# source_eagle.net
KiCad netlist of a schematic drawn in EAGLE
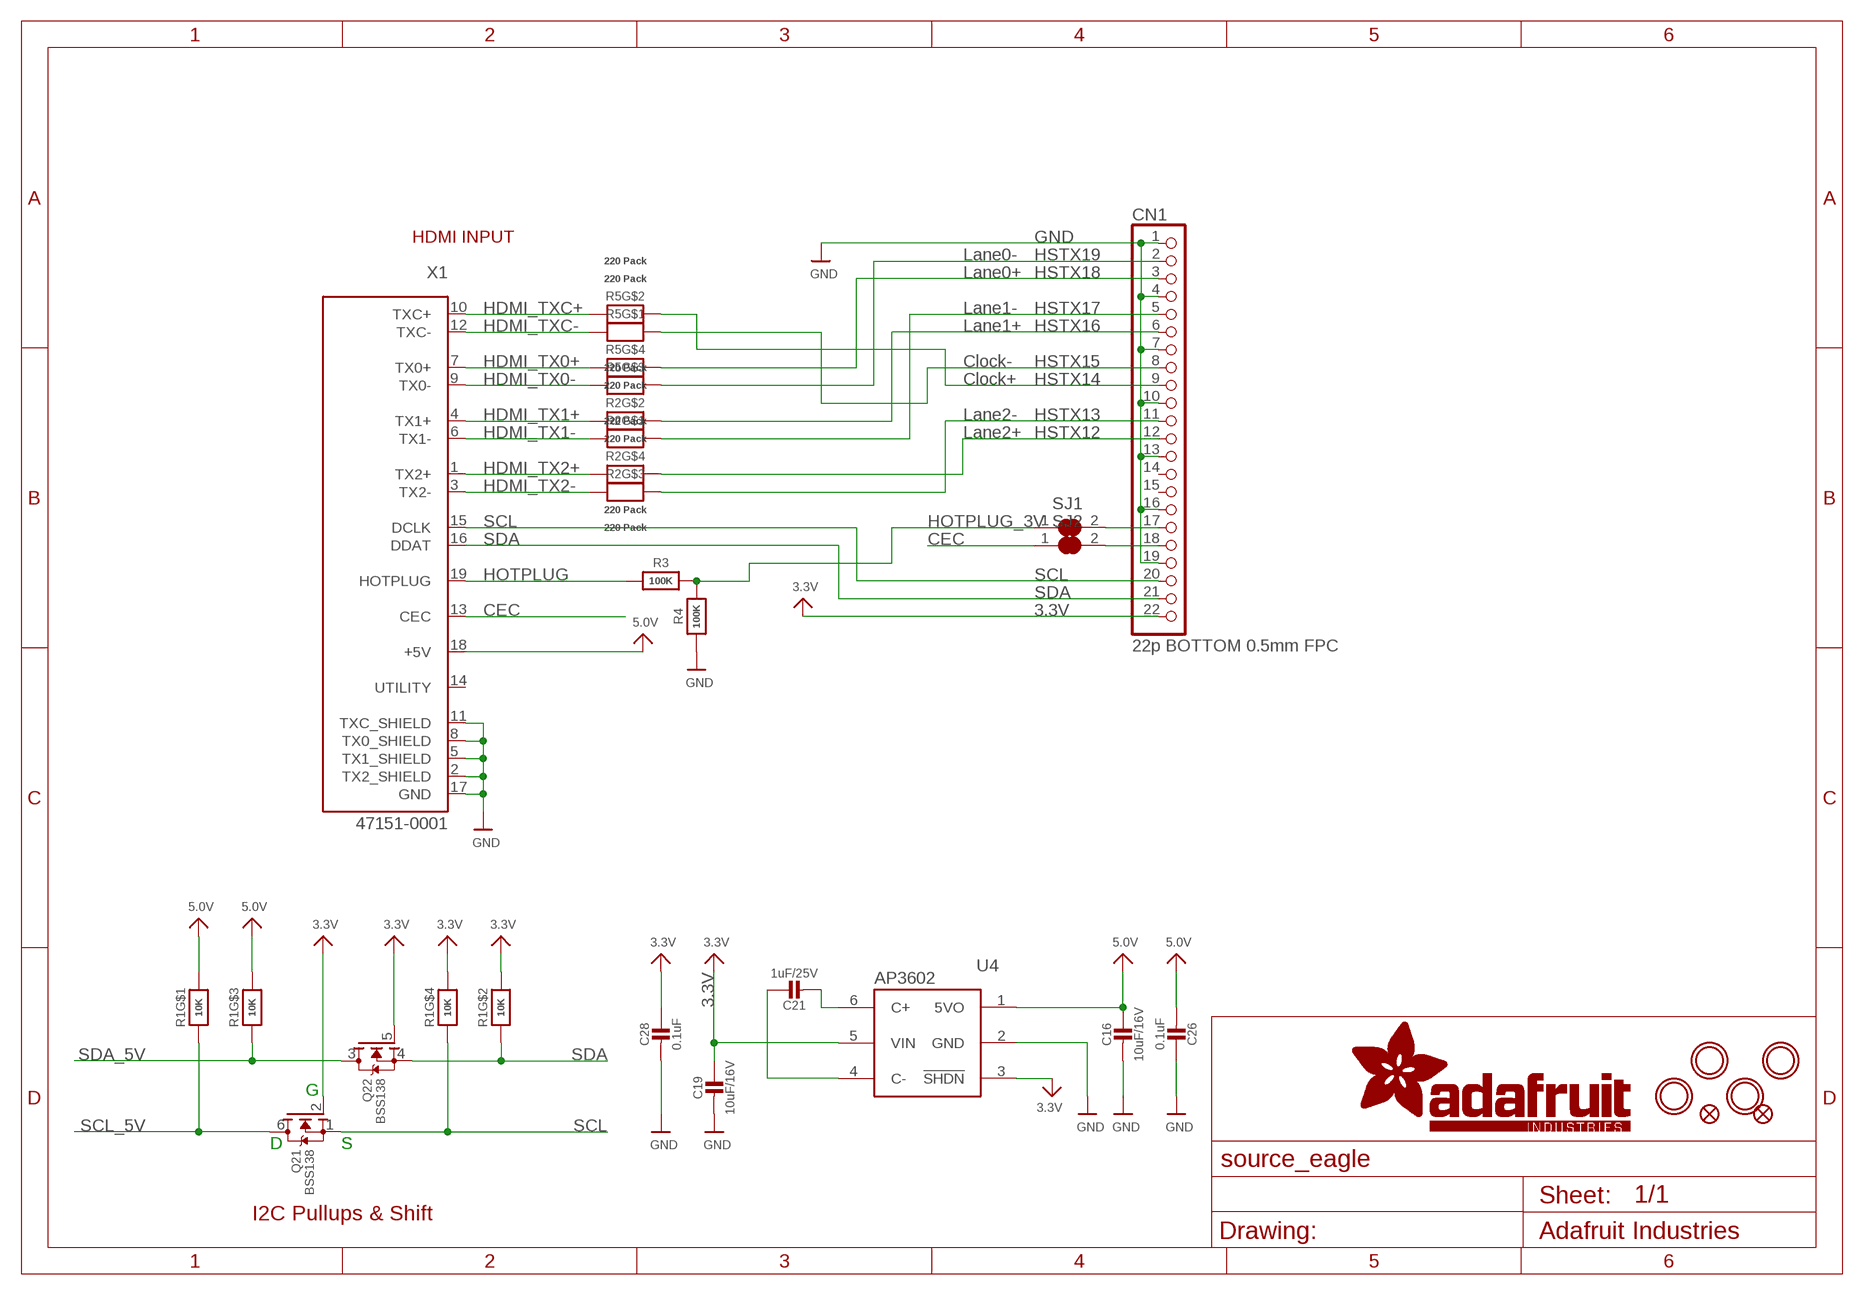
[diagram p0: schematic, sheet 1]

(export (version "E")
  (design (tool "Eeschema 10.0.6"))
  (components
    (comp (ref "C16")
      (value "10uF/16V")
      (footprint "eagle-import:0805-NO")
      (libsource (lib "eagle-import") (part "CAP_CERAMIC0805-NOOUTLINE"))
    )
    (comp (ref "C19")
      (value "10uF/16V")
      (footprint "eagle-import:0805-NO")
      (libsource (lib "eagle-import") (part "CAP_CERAMIC0805-NOOUTLINE"))
    )
    (comp (ref "C21")
      (value "1uF/25V")
      (footprint "eagle-import:0603-NO")
      (libsource (lib "eagle-import") (part "CAP_CERAMIC0603_NO"))
    )
    (comp (ref "C26")
      (value "0.1uF")
      (footprint "eagle-import:0603-NO")
      (libsource (lib "eagle-import") (part "CAP_CERAMIC0603_NO"))
    )
    (comp (ref "C28")
      (value "0.1uF")
      (footprint "eagle-import:0603-NO")
      (libsource (lib "eagle-import") (part "CAP_CERAMIC0603_NO"))
    )
    (comp (ref "CN1")
      (value "22p BOTTOM 0.5mm FPC")
      (footprint "eagle-import:FPC_22PIN")
      (libsource (lib "eagle-import") (part "HEADER-1X22_22PIN_0.5MM_BOT"))
    )
    (comp (ref "FID1")
      (value "FIDUCIAL_1MM")
      (footprint "eagle-import:FIDUCIAL_1MM")
      (libsource (lib "eagle-import") (part "FIDUCIAL_1MM"))
    )
    (comp (ref "FID2")
      (value "FIDUCIAL_1MM")
      (footprint "eagle-import:FIDUCIAL_1MM")
      (libsource (lib "eagle-import") (part "FIDUCIAL_1MM"))
    )
    (comp (ref "Q2")
      (value "BSS138")
      (footprint "eagle-import:SOT363")
      (libsource (lib "eagle-import") (part "MOSFET-N_DUAL"))
    )
    (comp (ref "R1")
      (value "10K")
      (footprint "eagle-import:RESPACK_4X0603")
      (libsource (lib "eagle-import") (part "RESISTOR_4PACK"))
    )
    (comp (ref "R2")
      (value "220 Pack")
      (footprint "eagle-import:RESPACK_4X0603")
      (libsource (lib "eagle-import") (part "RESISTOR_4PACK"))
    )
    (comp (ref "R3")
      (value "100K")
      (footprint "eagle-import:0603-NO")
      (libsource (lib "eagle-import") (part "RESISTOR_0603_NOOUT"))
    )
    (comp (ref "R4")
      (value "100K")
      (footprint "eagle-import:0603-NO")
      (libsource (lib "eagle-import") (part "RESISTOR_0603_NOOUT"))
    )
    (comp (ref "R5")
      (value "220 Pack")
      (footprint "eagle-import:RESPACK_4X0603")
      (libsource (lib "eagle-import") (part "RESISTOR_4PACK"))
    )
    (comp (ref "SJ1")
      (value "SOLDERJUMPER_CLOSED")
      (footprint "eagle-import:SOLDERJUMPER_CLOSEDWIRE")
      (libsource (lib "eagle-import") (part "SOLDERJUMPER_CLOSED"))
    )
    (comp (ref "SJ2")
      (value "SOLDERJUMPER_CLOSED")
      (footprint "eagle-import:SOLDERJUMPER_CLOSEDWIRE")
      (libsource (lib "eagle-import") (part "SOLDERJUMPER_CLOSED"))
    )
    (comp (ref "U$2")
      (value "MOUNTINGHOLE2.5")
      (footprint "eagle-import:MOUNTINGHOLE_2.5_PLATED")
      (libsource (lib "eagle-import") (part "MOUNTINGHOLE2.5"))
    )
    (comp (ref "U$3")
      (value "MOUNTINGHOLE2.5")
      (footprint "eagle-import:MOUNTINGHOLE_2.5_PLATED")
      (libsource (lib "eagle-import") (part "MOUNTINGHOLE2.5"))
    )
    (comp (ref "U$5")
      (value "MOUNTINGHOLE2.5")
      (footprint "eagle-import:MOUNTINGHOLE_2.5_PLATED")
      (libsource (lib "eagle-import") (part "MOUNTINGHOLE2.5"))
    )
    (comp (ref "U$7")
      (value "MOUNTINGHOLE2.5")
      (footprint "eagle-import:MOUNTINGHOLE_2.5_PLATED")
      (libsource (lib "eagle-import") (part "MOUNTINGHOLE2.5"))
    )
    (comp (ref "U4")
      (value "AP3602")
      (footprint "eagle-import:SOT23-6")
      (libsource (lib "eagle-import") (part "AP3602"))
    )
    (comp (ref "X1")
      (value "47151-0001")
      (footprint "eagle-import:HDMI_MOLEX_47151-0001")
      (libsource (lib "eagle-import") (part "HDMI_MOLEX_47151"))
    )
  )
  (nets
    (net (code "1") (name "/CEC") (class "Default")
      (node (ref "SJ2") (pin "1") (pinfunction "1_1") (pintype "passive"))
      (node (ref "X1") (pin "13") (pinfunction "CEC_13") (pintype "bidirectional"))
    )
    (net (code "2") (name "/HDMI_TX0+") (class "Default")
      (node (ref "R5") (pin "4") (pinfunction "1_4") (pintype "passive"))
      (node (ref "X1") (pin "7") (pinfunction "TX0+_7") (pintype "bidirectional"))
    )
    (net (code "3") (name "/HDMI_TX0-") (class "Default")
      (node (ref "R5") (pin "3") (pinfunction "1_3") (pintype "passive"))
      (node (ref "X1") (pin "9") (pinfunction "TX0-_9") (pintype "bidirectional"))
    )
    (net (code "4") (name "/HDMI_TX1+") (class "Default")
      (node (ref "R2") (pin "2") (pinfunction "1_2") (pintype "passive"))
      (node (ref "X1") (pin "4") (pinfunction "TX1+_4") (pintype "bidirectional"))
    )
    (net (code "5") (name "/HDMI_TX1-") (class "Default")
      (node (ref "R2") (pin "1") (pinfunction "1_1") (pintype "passive"))
      (node (ref "X1") (pin "6") (pinfunction "TX1-_6") (pintype "bidirectional"))
    )
    (net (code "6") (name "/HDMI_TX2+") (class "Default")
      (node (ref "R2") (pin "4") (pinfunction "1_4") (pintype "passive"))
      (node (ref "X1") (pin "1") (pinfunction "TX2+_1") (pintype "bidirectional"))
    )
    (net (code "7") (name "/HDMI_TX2-") (class "Default")
      (node (ref "R2") (pin "3") (pinfunction "1_3") (pintype "passive"))
      (node (ref "X1") (pin "3") (pinfunction "TX2-_3") (pintype "bidirectional"))
    )
    (net (code "8") (name "/HDMI_TXC+") (class "Default")
      (node (ref "R5") (pin "2") (pinfunction "1_2") (pintype "passive"))
      (node (ref "X1") (pin "10") (pinfunction "TXC+_10") (pintype "bidirectional"))
    )
    (net (code "9") (name "/HDMI_TXC-") (class "Default")
      (node (ref "R5") (pin "1") (pinfunction "1_1") (pintype "passive"))
      (node (ref "X1") (pin "12") (pinfunction "TXC-_12") (pintype "bidirectional"))
    )
    (net (code "10") (name "/HOTPLUG") (class "Default")
      (node (ref "R3") (pin "1") (pinfunction "1_1") (pintype "passive"))
      (node (ref "X1") (pin "19") (pinfunction "HOTPLUG_19") (pintype "bidirectional"))
    )
    (net (code "11") (name "/HOTPLUG_3V") (class "Default")
      (node (ref "R3") (pin "2") (pinfunction "2_2") (pintype "passive"))
      (node (ref "R4") (pin "2") (pinfunction "2_2") (pintype "passive"))
      (node (ref "SJ1") (pin "1") (pinfunction "1_1") (pintype "passive"))
    )
    (net (code "12") (name "/HSTX12") (class "Default")
      (node (ref "CN1") (pin "12") (pinfunction "12_12") (pintype "passive"))
      (node (ref "R2") (pin "5") (pinfunction "2_5") (pintype "passive"))
    )
    (net (code "13") (name "/HSTX13") (class "Default")
      (node (ref "CN1") (pin "11") (pinfunction "11_11") (pintype "passive"))
      (node (ref "R2") (pin "6") (pinfunction "2_6") (pintype "passive"))
    )
    (net (code "14") (name "/HSTX14") (class "Default")
      (node (ref "CN1") (pin "9") (pinfunction "9_9") (pintype "passive"))
      (node (ref "R5") (pin "7") (pinfunction "2_7") (pintype "passive"))
    )
    (net (code "15") (name "/HSTX15") (class "Default")
      (node (ref "CN1") (pin "8") (pinfunction "8_8") (pintype "passive"))
      (node (ref "R5") (pin "8") (pinfunction "2_8") (pintype "passive"))
    )
    (net (code "16") (name "/HSTX16") (class "Default")
      (node (ref "CN1") (pin "6") (pinfunction "6_6") (pintype "passive"))
      (node (ref "R2") (pin "7") (pinfunction "2_7") (pintype "passive"))
    )
    (net (code "17") (name "/HSTX17") (class "Default")
      (node (ref "CN1") (pin "5") (pinfunction "5_5") (pintype "passive"))
      (node (ref "R2") (pin "8") (pinfunction "2_8") (pintype "passive"))
    )
    (net (code "18") (name "/HSTX18") (class "Default")
      (node (ref "CN1") (pin "3") (pinfunction "3_3") (pintype "passive"))
      (node (ref "R5") (pin "5") (pinfunction "2_5") (pintype "passive"))
    )
    (net (code "19") (name "/HSTX19") (class "Default")
      (node (ref "CN1") (pin "2") (pinfunction "2_2") (pintype "passive"))
      (node (ref "R5") (pin "6") (pinfunction "2_6") (pintype "passive"))
    )
    (net (code "20") (name "/SCL") (class "Default")
      (node (ref "CN1") (pin "20") (pinfunction "20_20") (pintype "passive"))
      (node (ref "Q2") (pin "1") (pinfunction "S_1") (pintype "bidirectional"))
      (node (ref "R1") (pin "4") (pinfunction "1_4") (pintype "passive"))
      (node (ref "X1") (pin "15") (pinfunction "DCLK_15") (pintype "bidirectional"))
    )
    (net (code "21") (name "/SCL_5V") (class "Default")
      (node (ref "Q2") (pin "6") (pinfunction "D_6") (pintype "bidirectional"))
      (node (ref "R1") (pin "1") (pinfunction "1_1") (pintype "passive"))
    )
    (net (code "22") (name "/SDA") (class "Default")
      (node (ref "CN1") (pin "21") (pinfunction "21_21") (pintype "passive"))
      (node (ref "Q2") (pin "4") (pinfunction "S_4") (pintype "bidirectional"))
      (node (ref "R1") (pin "2") (pinfunction "1_2") (pintype "passive"))
      (node (ref "X1") (pin "16") (pinfunction "DDAT_16") (pintype "bidirectional"))
    )
    (net (code "23") (name "/SDA_5V") (class "Default")
      (node (ref "Q2") (pin "3") (pinfunction "D_3") (pintype "bidirectional"))
      (node (ref "R1") (pin "3") (pinfunction "1_3") (pintype "passive"))
    )
    (net (code "24") (name "3.3V") (class "Default")
      (node (ref "C19") (pin "1") (pinfunction "1_1") (pintype "passive"))
      (node (ref "C28") (pin "1") (pinfunction "1_1") (pintype "passive"))
      (node (ref "CN1") (pin "22") (pinfunction "22_22") (pintype "passive"))
      (node (ref "Q2") (pin "2") (pinfunction "G_2") (pintype "bidirectional"))
      (node (ref "Q2") (pin "5") (pinfunction "G_5") (pintype "bidirectional"))
      (node (ref "R1") (pin "5") (pinfunction "2_5") (pintype "passive"))
      (node (ref "R1") (pin "7") (pinfunction "2_7") (pintype "passive"))
      (node (ref "U4") (pin "3") (pinfunction "~{SHDN}_3") (pintype "input"))
      (node (ref "U4") (pin "5") (pinfunction "VIN_5") (pintype "power_in"))
    )
    (net (code "25") (name "5.0V") (class "Default")
      (node (ref "C16") (pin "1") (pinfunction "1_1") (pintype "passive"))
      (node (ref "C26") (pin "2") (pinfunction "2_2") (pintype "passive"))
      (node (ref "R1") (pin "6") (pinfunction "2_6") (pintype "passive"))
      (node (ref "R1") (pin "8") (pinfunction "2_8") (pintype "passive"))
      (node (ref "U4") (pin "1") (pinfunction "5VO_1") (pintype "power_in"))
      (node (ref "X1") (pin "18") (pinfunction "+5V_18") (pintype "power_in"))
    )
    (net (code "26") (name "GND") (class "Default")
      (node (ref "C16") (pin "2") (pinfunction "2_2") (pintype "passive"))
      (node (ref "C19") (pin "2") (pinfunction "2_2") (pintype "passive"))
      (node (ref "C26") (pin "1") (pinfunction "1_1") (pintype "passive"))
      (node (ref "C28") (pin "2") (pinfunction "2_2") (pintype "passive"))
      (node (ref "CN1") (pin "1") (pinfunction "1_1") (pintype "passive"))
      (node (ref "CN1") (pin "10") (pinfunction "10_10") (pintype "passive"))
      (node (ref "CN1") (pin "13") (pinfunction "13_13") (pintype "passive"))
      (node (ref "CN1") (pin "16") (pinfunction "16_16") (pintype "passive"))
      (node (ref "CN1") (pin "19") (pinfunction "19_19") (pintype "passive"))
      (node (ref "CN1") (pin "4") (pinfunction "4_4") (pintype "passive"))
      (node (ref "CN1") (pin "7") (pinfunction "7_7") (pintype "passive"))
      (node (ref "R4") (pin "1") (pinfunction "1_1") (pintype "passive"))
      (node (ref "U4") (pin "2") (pinfunction "GND_2") (pintype "power_in"))
      (node (ref "X1") (pin "11") (pinfunction "TXC_SHIELD_11") (pintype "power_in"))
      (node (ref "X1") (pin "17") (pinfunction "GND_17") (pintype "power_in"))
      (node (ref "X1") (pin "2") (pinfunction "TX2_SHIELD_2") (pintype "power_in"))
      (node (ref "X1") (pin "5") (pinfunction "TX1_SHIELD_5") (pintype "power_in"))
      (node (ref "X1") (pin "8") (pinfunction "TX0_SHIELD_8") (pintype "power_in"))
    )
    (net (code "27") (name "Net-(CN1-Pad17)") (class "Default")
      (node (ref "CN1") (pin "17") (pinfunction "17_17") (pintype "passive"))
      (node (ref "SJ1") (pin "2") (pinfunction "2_2") (pintype "passive"))
    )
    (net (code "28") (name "Net-(CN1-Pad18)") (class "Default")
      (node (ref "CN1") (pin "18") (pinfunction "18_18") (pintype "passive"))
      (node (ref "SJ2") (pin "2") (pinfunction "2_2") (pintype "passive"))
    )
    (net (code "29") (name "Net-(U4-C+)") (class "Default")
      (node (ref "C21") (pin "2") (pinfunction "2_2") (pintype "passive"))
      (node (ref "U4") (pin "6") (pinfunction "C+_6") (pintype "bidirectional"))
    )
    (net (code "30") (name "Net-(U4-C-)") (class "Default")
      (node (ref "C21") (pin "1") (pinfunction "1_1") (pintype "passive"))
      (node (ref "U4") (pin "4") (pinfunction "C-_4") (pintype "bidirectional"))
    )
    (net (code "31") (name "unconnected-(CN1-Pad14)") (class "Default")
      (node (ref "CN1") (pin "14") (pinfunction "14_14") (pintype "passive"))
    )
    (net (code "32") (name "unconnected-(CN1-Pad15)") (class "Default")
      (node (ref "CN1") (pin "15") (pinfunction "15_15") (pintype "passive"))
    )
    (net (code "33") (name "unconnected-(X1A-UTILITY-Pad14)") (class "Default")
      (node (ref "X1") (pin "14") (pinfunction "UTILITY_14") (pintype "bidirectional"))
    )
  )
)
